# Main.net
KiCad netlist of a schematic drawn in Altium Designer
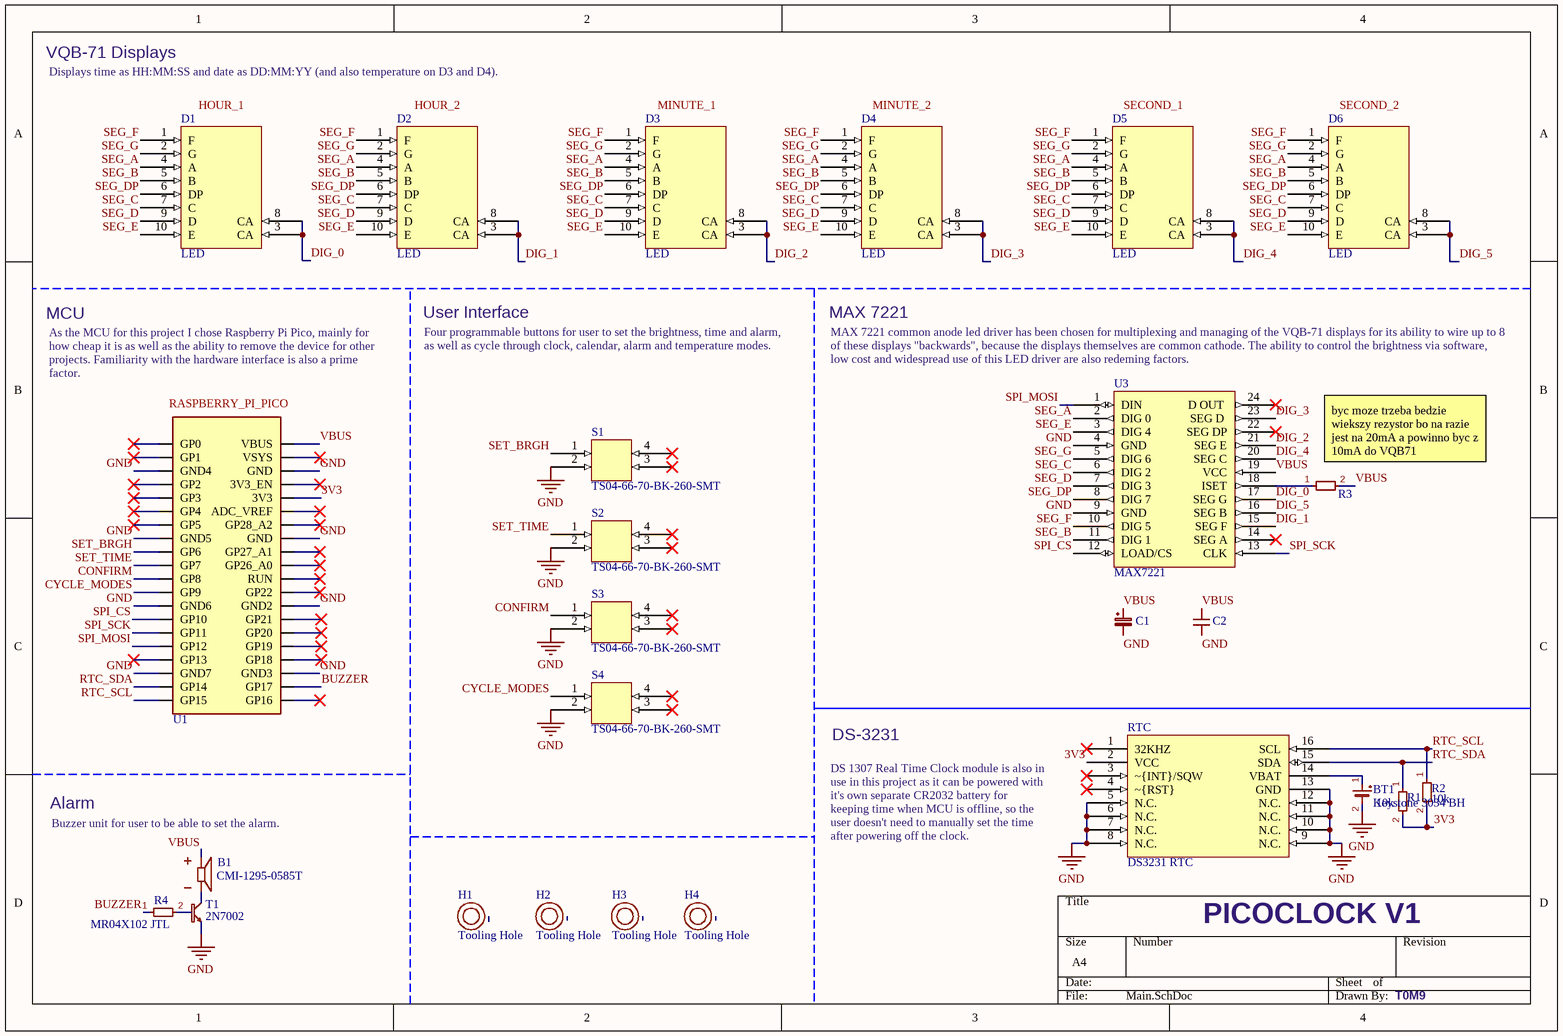
[diagram p0: Main.SchDoc]

(export (version "E")
  (design (tool "Eeschema 10.0.6"))
  (components
    (comp (ref "B1")
      (value "CMI-1295-0585T")
      (footprint "CMI-1295-0585T")
      (description "Buzzer")
      (libsource (lib "Schlib1") (part "CMI-1295-0585T"))
    )
    (comp (ref "BT1")
      (value "Keystone 3034 BH")
      (footprint "BAT_3034TR")
      (libsource (lib "Schlib1") (part "Keystone 3034 BH"))
    )
    (comp (ref "C1")
      (value "Electrolitic Capacitor 10uF")
      (footprint "CAPC2012X145N")
      (description "CGA4J1X7R0J106K125AC \r\n\r\n10u 6.3V 0805")
      (libsource (lib "Schlib1") (part "Electrolitic Capacitor 10uF"))
    )
    (comp (ref "C2")
      (value "UMK105B7104KVHF")
      (footprint "UMK105B7104KVHF")
      (description "0.1uF")
      (libsource (lib "Schlib1") (part "UMK105B7104KVHF"))
    )
    (comp (ref "D1")
      (value "LED")
      (footprint "LED_INND-TS56RAB")
      (description "VQB-71")
      (libsource (lib "Schlib1") (part "LED"))
    )
    (comp (ref "D2")
      (value "LED")
      (footprint "LED_INND-TS56RAB")
      (description "VQB-71")
      (libsource (lib "Schlib1") (part "LED"))
    )
    (comp (ref "D3")
      (value "LED")
      (footprint "LED_INND-TS56RAB")
      (description "VQB-71")
      (libsource (lib "Schlib1") (part "LED"))
    )
    (comp (ref "D4")
      (value "LED")
      (footprint "LED_INND-TS56RAB")
      (description "VQB-71")
      (libsource (lib "Schlib1") (part "LED"))
    )
    (comp (ref "D5")
      (value "LED")
      (footprint "LED_INND-TS56RAB")
      (description "VQB-71")
      (libsource (lib "Schlib1") (part "LED"))
    )
    (comp (ref "D6")
      (value "LED")
      (footprint "LED_INND-TS56RAB")
      (description "VQB-71")
      (libsource (lib "Schlib1") (part "LED"))
    )
    (comp (ref "H1")
      (value "Tooling Hole")
      (footprint "Tooling Hole")
      (libsource (lib "Schlib1") (part "Tooling Hole"))
    )
    (comp (ref "H2")
      (value "Tooling Hole")
      (footprint "Tooling Hole")
      (libsource (lib "Schlib1") (part "Tooling Hole"))
    )
    (comp (ref "H3")
      (value "Tooling Hole")
      (footprint "Tooling Hole")
      (libsource (lib "Schlib1") (part "Tooling Hole"))
    )
    (comp (ref "H4")
      (value "Tooling Hole")
      (footprint "Tooling Hole")
      (libsource (lib "Schlib1") (part "Tooling Hole"))
    )
    (comp (ref "R1")
      (value "10k")
      (footprint "MR04X102 JTL")
      (libsource (lib "Schlib1") (part "ESR01MZPF1002"))
    )
    (comp (ref "R2")
      (value "10k")
      (footprint "MR04X102 JTL")
      (libsource (lib "Schlib1") (part "ESR01MZPF1002"))
    )
    (comp (ref "R3")
      (value "CRCW040221K0FKEDC")
      (footprint "CRCW040221K0FKEDC")
      (description "21k")
      (libsource (lib "Schlib1") (part "CRCW040221K0FKEDC"))
    )
    (comp (ref "R4")
      (value "MR04X102 JTL")
      (footprint "MR04X102 JTL")
      (description "1k")
      (libsource (lib "Schlib1") (part "MR04X102 JTL"))
    )
    (comp (ref "RTC")
      (value "DS3231 RTC")
      (footprint "DS3231 RTC")
      (libsource (lib "Schlib1") (part "DS3231 RTC"))
    )
    (comp (ref "S1")
      (value "TS04-66-70-BK-260-SMT")
      (footprint "TS04-66-70-BK-260-SMT")
      (description "50mA 12VDC")
      (libsource (lib "Schlib1") (part "TS04-66-70-BK-260-SMT"))
    )
    (comp (ref "S2")
      (value "TS04-66-70-BK-260-SMT")
      (footprint "TS04-66-70-BK-260-SMT")
      (description "50mA 12VDC")
      (libsource (lib "Schlib1") (part "TS04-66-70-BK-260-SMT"))
    )
    (comp (ref "S3")
      (value "TS04-66-70-BK-260-SMT")
      (footprint "TS04-66-70-BK-260-SMT")
      (description "50mA 12VDC")
      (libsource (lib "Schlib1") (part "TS04-66-70-BK-260-SMT"))
    )
    (comp (ref "S4")
      (value "TS04-66-70-BK-260-SMT")
      (footprint "TS04-66-70-BK-260-SMT")
      (description "50mA 12VDC")
      (libsource (lib "Schlib1") (part "TS04-66-70-BK-260-SMT"))
    )
    (comp (ref "T1")
      (value "2N7002")
      (footprint "2N7002")
      (description "Transistor")
      (libsource (lib "Schlib1") (part "2N7002"))
    )
    (comp (ref "U1")
      (value "RASPBERRY_PI_PICO")
      (footprint "RASPBERRY_PI_PICO")
      (fields (field (name "MF") "Raspberry Pi") (field (name "MP") "RASPBERRY PI PICO"))
      (libsource (lib "Schlib1") (part "RASPBERRY_PI_PICO"))
    )
    (comp (ref "U3") (value "MAX7221") (footprint "MAX7221") (libsource (lib "Schlib1") (part "MAX7221")))
  )
  (nets
    (net (code "1") (name "/3V3") (class "Default")
      (node (ref "R1") (pin "2") (pinfunction "2_2") (pintype "passive"))
      (node (ref "R2") (pin "2") (pinfunction "2_2") (pintype "passive"))
      (node (ref "RTC") (pin "2") (pinfunction "VCC_2") (pintype "power_in"))
      (node (ref "U1") (pin "3V3") (pinfunction "3V3_3V3") (pintype "power_in"))
    )
    (net (code "2") (name "/BUZZER") (class "Default")
      (node (ref "R4") (pin "1") (pinfunction "1_1") (pintype "passive"))
      (node (ref "U1") (pin "GP17") (pinfunction "GP17_GP17") (pintype "bidirectional"))
    )
    (net (code "3") (name "/CONFIRM") (class "Default")
      (node (ref "S3") (pin "1") (pintype "input"))
      (node (ref "U1") (pin "GP8") (pinfunction "GP8_GP8") (pintype "bidirectional"))
    )
    (net (code "4") (name "/CYCLE_MODES") (class "Default")
      (node (ref "S4") (pin "1") (pintype "input"))
      (node (ref "U1") (pin "GP9") (pinfunction "GP9_GP9") (pintype "bidirectional"))
    )
    (net (code "5") (name "/DIG_0") (class "Default")
      (node (ref "D1") (pin "3") (pinfunction "CA_3") (pintype "input"))
      (node (ref "D1") (pin "8") (pinfunction "CA_8") (pintype "input"))
      (node (ref "U3") (pin "17") (pinfunction "SEG_G_17") (pintype "output"))
    )
    (net (code "6") (name "/DIG_1") (class "Default")
      (node (ref "D2") (pin "3") (pinfunction "CA_3") (pintype "input"))
      (node (ref "D2") (pin "8") (pinfunction "CA_8") (pintype "input"))
      (node (ref "U3") (pin "15") (pinfunction "SEG_F_15") (pintype "output"))
    )
    (net (code "7") (name "/DIG_2") (class "Default")
      (node (ref "D3") (pin "3") (pinfunction "CA_3") (pintype "input"))
      (node (ref "D3") (pin "8") (pinfunction "CA_8") (pintype "input"))
      (node (ref "U3") (pin "21") (pinfunction "SEG_E_21") (pintype "output"))
    )
    (net (code "8") (name "/DIG_3") (class "Default")
      (node (ref "D4") (pin "3") (pinfunction "CA_3") (pintype "input"))
      (node (ref "D4") (pin "8") (pinfunction "CA_8") (pintype "input"))
      (node (ref "U3") (pin "23") (pinfunction "SEG_D_23") (pintype "output"))
    )
    (net (code "9") (name "/DIG_4") (class "Default")
      (node (ref "D5") (pin "3") (pinfunction "CA_3") (pintype "input"))
      (node (ref "D5") (pin "8") (pinfunction "CA_8") (pintype "input"))
      (node (ref "U3") (pin "20") (pinfunction "SEG_C_20") (pintype "output"))
    )
    (net (code "10") (name "/DIG_5") (class "Default")
      (node (ref "D6") (pin "3") (pinfunction "CA_3") (pintype "input"))
      (node (ref "D6") (pin "8") (pinfunction "CA_8") (pintype "input"))
      (node (ref "U3") (pin "16") (pinfunction "SEG_B_16") (pintype "output"))
    )
    (net (code "11") (name "/RTC_SCL") (class "Default")
      (node (ref "R2") (pin "1") (pinfunction "1_1") (pintype "passive"))
      (node (ref "RTC") (pin "16") (pinfunction "SCL_16") (pintype "input"))
      (node (ref "U1") (pin "GP15") (pinfunction "GP15_GP15") (pintype "bidirectional"))
    )
    (net (code "12") (name "/RTC_SDA") (class "Default")
      (node (ref "R1") (pin "1") (pinfunction "1_1") (pintype "passive"))
      (node (ref "RTC") (pin "15") (pinfunction "SDA_15") (pintype "bidirectional"))
      (node (ref "U1") (pin "GP14") (pinfunction "GP14_GP14") (pintype "bidirectional"))
    )
    (net (code "13") (name "/SEG_A") (class "Default")
      (node (ref "D1") (pin "4") (pinfunction "A_4") (pintype "input"))
      (node (ref "D2") (pin "4") (pinfunction "A_4") (pintype "input"))
      (node (ref "D3") (pin "4") (pinfunction "A_4") (pintype "input"))
      (node (ref "D4") (pin "4") (pinfunction "A_4") (pintype "input"))
      (node (ref "D5") (pin "4") (pinfunction "A_4") (pintype "input"))
      (node (ref "D6") (pin "4") (pinfunction "A_4") (pintype "input"))
      (node (ref "U3") (pin "2") (pinfunction "DIG_0_2") (pintype "output"))
    )
    (net (code "14") (name "/SEG_B") (class "Default")
      (node (ref "D1") (pin "5") (pinfunction "B_5") (pintype "input"))
      (node (ref "D2") (pin "5") (pinfunction "B_5") (pintype "input"))
      (node (ref "D3") (pin "5") (pinfunction "B_5") (pintype "input"))
      (node (ref "D4") (pin "5") (pinfunction "B_5") (pintype "input"))
      (node (ref "D5") (pin "5") (pinfunction "B_5") (pintype "input"))
      (node (ref "D6") (pin "5") (pinfunction "B_5") (pintype "input"))
      (node (ref "U3") (pin "11") (pinfunction "DIG_1_11") (pintype "output"))
    )
    (net (code "15") (name "/SEG_C") (class "Default")
      (node (ref "D1") (pin "7") (pinfunction "C_7") (pintype "input"))
      (node (ref "D2") (pin "7") (pinfunction "C_7") (pintype "input"))
      (node (ref "D3") (pin "7") (pinfunction "C_7") (pintype "input"))
      (node (ref "D4") (pin "7") (pinfunction "C_7") (pintype "input"))
      (node (ref "D5") (pin "7") (pinfunction "C_7") (pintype "input"))
      (node (ref "D6") (pin "7") (pinfunction "C_7") (pintype "input"))
      (node (ref "U3") (pin "6") (pinfunction "DIG_2_6") (pintype "output"))
    )
    (net (code "16") (name "/SEG_D") (class "Default")
      (node (ref "D1") (pin "9") (pinfunction "D_9") (pintype "input"))
      (node (ref "D2") (pin "9") (pinfunction "D_9") (pintype "input"))
      (node (ref "D3") (pin "9") (pinfunction "D_9") (pintype "input"))
      (node (ref "D4") (pin "9") (pinfunction "D_9") (pintype "input"))
      (node (ref "D5") (pin "9") (pinfunction "D_9") (pintype "input"))
      (node (ref "D6") (pin "9") (pinfunction "D_9") (pintype "input"))
      (node (ref "U3") (pin "7") (pinfunction "DIG_3_7") (pintype "output"))
    )
    (net (code "17") (name "/SEG_DP") (class "Default")
      (node (ref "D1") (pin "6") (pinfunction "DP_6") (pintype "input"))
      (node (ref "D2") (pin "6") (pinfunction "DP_6") (pintype "input"))
      (node (ref "D3") (pin "6") (pinfunction "DP_6") (pintype "input"))
      (node (ref "D4") (pin "6") (pinfunction "DP_6") (pintype "input"))
      (node (ref "D5") (pin "6") (pinfunction "DP_6") (pintype "input"))
      (node (ref "D6") (pin "6") (pinfunction "DP_6") (pintype "input"))
      (node (ref "U3") (pin "8") (pinfunction "DIG_7_8") (pintype "output"))
    )
    (net (code "18") (name "/SEG_E") (class "Default")
      (node (ref "D1") (pin "10") (pinfunction "E_10") (pintype "input"))
      (node (ref "D2") (pin "10") (pinfunction "E_10") (pintype "input"))
      (node (ref "D3") (pin "10") (pinfunction "E_10") (pintype "input"))
      (node (ref "D4") (pin "10") (pinfunction "E_10") (pintype "input"))
      (node (ref "D5") (pin "10") (pinfunction "E_10") (pintype "input"))
      (node (ref "D6") (pin "10") (pinfunction "E_10") (pintype "input"))
      (node (ref "U3") (pin "3") (pinfunction "DIG_4_3") (pintype "output"))
    )
    (net (code "19") (name "/SEG_F") (class "Default")
      (node (ref "D1") (pin "1") (pinfunction "F_1") (pintype "input"))
      (node (ref "D2") (pin "1") (pinfunction "F_1") (pintype "input"))
      (node (ref "D3") (pin "1") (pinfunction "F_1") (pintype "input"))
      (node (ref "D4") (pin "1") (pinfunction "F_1") (pintype "input"))
      (node (ref "D5") (pin "1") (pinfunction "F_1") (pintype "input"))
      (node (ref "D6") (pin "1") (pinfunction "F_1") (pintype "input"))
      (node (ref "U3") (pin "10") (pinfunction "DIG_5_10") (pintype "output"))
    )
    (net (code "20") (name "/SEG_G") (class "Default")
      (node (ref "D1") (pin "2") (pinfunction "G_2") (pintype "input"))
      (node (ref "D2") (pin "2") (pinfunction "G_2") (pintype "input"))
      (node (ref "D3") (pin "2") (pinfunction "G_2") (pintype "input"))
      (node (ref "D4") (pin "2") (pinfunction "G_2") (pintype "input"))
      (node (ref "D5") (pin "2") (pinfunction "G_2") (pintype "input"))
      (node (ref "D6") (pin "2") (pinfunction "G_2") (pintype "input"))
      (node (ref "U3") (pin "5") (pinfunction "DIG_6_5") (pintype "output"))
    )
    (net (code "21") (name "/SET_BRGH") (class "Default")
      (node (ref "S1") (pin "1") (pintype "input"))
      (node (ref "U1") (pin "GP6") (pinfunction "GP6_GP6") (pintype "bidirectional"))
    )
    (net (code "22") (name "/SET_TIME") (class "Default")
      (node (ref "S2") (pin "1") (pintype "input"))
      (node (ref "U1") (pin "GP7") (pinfunction "GP7_GP7") (pintype "bidirectional"))
    )
    (net (code "23") (name "/SPI_CS") (class "Default")
      (node (ref "U1") (pin "GP10") (pinfunction "GP10_GP10") (pintype "bidirectional"))
      (node (ref "U3") (pin "12") (pinfunction "LOAD/CS_12") (pintype "bidirectional"))
    )
    (net (code "24") (name "/SPI_MOSI") (class "Default")
      (node (ref "U1") (pin "GP12") (pinfunction "GP12_GP12") (pintype "bidirectional"))
      (node (ref "U3") (pin "1") (pinfunction "DIN_1") (pintype "bidirectional"))
    )
    (net (code "25") (name "/SPI_SCK") (class "Default")
      (node (ref "U1") (pin "GP11") (pinfunction "GP11_GP11") (pintype "bidirectional"))
      (node (ref "U3") (pin "13") (pinfunction "CLK_13") (pintype "input"))
    )
    (net (code "26") (name "/VBUS") (class "Default")
      (node (ref "B1") (pin "P") (pinfunction "P_P") (pintype "passive"))
      (node (ref "C1") (pin "1") (pinfunction "1_1") (pintype "passive"))
      (node (ref "C2") (pin "1") (pinfunction "1_1") (pintype "passive"))
      (node (ref "R3") (pin "2") (pinfunction "2_2") (pintype "passive"))
      (node (ref "U1") (pin "VBUS") (pinfunction "VBUS_VBUS") (pintype "bidirectional"))
      (node (ref "U3") (pin "19") (pinfunction "VCC_19") (pintype "input"))
    )
    (net (code "27") (name "GND") (class "Default")
      (node (ref "BT1") (pin "2") (pinfunction "2_2") (pintype "passive"))
      (node (ref "C1") (pin "2") (pinfunction "2_2") (pintype "passive"))
      (node (ref "C2") (pin "2") (pinfunction "2_2") (pintype "passive"))
      (node (ref "RTC") (pin "10") (pinfunction "N.C._10") (pintype "input"))
      (node (ref "RTC") (pin "11") (pinfunction "N.C._11") (pintype "input"))
      (node (ref "RTC") (pin "12") (pinfunction "N.C._12") (pintype "input"))
      (node (ref "RTC") (pin "13") (pinfunction "GND_13") (pintype "power_in"))
      (node (ref "RTC") (pin "5") (pinfunction "N.C._5") (pintype "input"))
      (node (ref "RTC") (pin "6") (pinfunction "N.C._6") (pintype "input"))
      (node (ref "RTC") (pin "7") (pinfunction "N.C._7") (pintype "input"))
      (node (ref "RTC") (pin "8") (pinfunction "N.C._8") (pintype "input"))
      (node (ref "RTC") (pin "9") (pinfunction "N.C._9") (pintype "input"))
      (node (ref "S1") (pin "2") (pintype "input"))
      (node (ref "S2") (pin "2") (pintype "input"))
      (node (ref "S3") (pin "2") (pintype "input"))
      (node (ref "S4") (pin "2") (pintype "input"))
      (node (ref "T1") (pin "2") (pinfunction "S_2") (pintype "passive"))
      (node (ref "U1") (pin "GND") (pinfunction "GND_GND") (pintype "passive"))
      (node (ref "U1") (pin "GND2") (pinfunction "GND2_GND2") (pintype "passive"))
      (node (ref "U1") (pin "GND3") (pinfunction "GND3_GND3") (pintype "passive"))
      (node (ref "U1") (pin "GND4") (pinfunction "GND4_GND4") (pintype "passive"))
      (node (ref "U1") (pin "GND5") (pinfunction "GND5_GND5") (pintype "passive"))
      (node (ref "U1") (pin "GND6") (pinfunction "GND6_GND6") (pintype "passive"))
      (node (ref "U1") (pin "GND7") (pinfunction "GND7_GND7") (pintype "passive"))
      (node (ref "U3") (pin "4") (pinfunction "GND_4") (pintype "input"))
      (node (ref "U3") (pin "9") (pinfunction "GND_9") (pintype "input"))
    )
    (net (code "28") (name "Net-(RTC-VBAT)") (class "Default")
      (node (ref "BT1") (pin "1") (pinfunction "1_1") (pintype "passive"))
      (node (ref "RTC") (pin "14") (pinfunction "VBAT_14") (pintype "power_in"))
    )
    (net (code "29") (name "Net-(T1-D)") (class "Default")
      (node (ref "B1") (pin "N") (pinfunction "N_N") (pintype "passive"))
      (node (ref "T1") (pin "3") (pinfunction "D_3") (pintype "passive"))
    )
    (net (code "30") (name "Net-(T1-G)") (class "Default")
      (node (ref "R4") (pin "2") (pinfunction "2_2") (pintype "passive"))
      (node (ref "T1") (pin "1") (pinfunction "G_1") (pintype "passive"))
    )
    (net (code "31") (name "Net-(U3-ISET)") (class "Default")
      (node (ref "R3") (pin "1") (pinfunction "1_1") (pintype "passive"))
      (node (ref "U3") (pin "18") (pinfunction "ISET_18") (pintype "output"))
    )
    (net (code "32") (name "unconnected-(RTC-32KHZ-Pad1)") (class "Default")
      (node (ref "RTC") (pin "1") (pinfunction "32KHZ_1") (pintype "open_collector+no_connect"))
    )
    (net (code "33") (name "unconnected-(RTC-~{INT}{slash}SQW-Pad3)") (class "Default")
      (node (ref "RTC") (pin "3") (pinfunction "~{INT}/SQW_3") (pintype "input+no_connect"))
    )
    (net (code "34") (name "unconnected-(RTC-~{RST}-Pad4)") (class "Default")
      (node (ref "RTC") (pin "4") (pinfunction "~{RST}_4") (pintype "input+no_connect"))
    )
    (net (code "35") (name "unconnected-(S1-Pad3)") (class "Default")
      (node (ref "S1") (pin "3") (pintype "input+no_connect"))
    )
    (net (code "36") (name "unconnected-(S1-Pad4)") (class "Default")
      (node (ref "S1") (pin "4") (pintype "input+no_connect"))
    )
    (net (code "37") (name "unconnected-(S2-Pad3)") (class "Default")
      (node (ref "S2") (pin "3") (pintype "input+no_connect"))
    )
    (net (code "38") (name "unconnected-(S2-Pad4)") (class "Default")
      (node (ref "S2") (pin "4") (pintype "input+no_connect"))
    )
    (net (code "39") (name "unconnected-(S3-Pad3)") (class "Default")
      (node (ref "S3") (pin "3") (pintype "input+no_connect"))
    )
    (net (code "40") (name "unconnected-(S3-Pad4)") (class "Default")
      (node (ref "S3") (pin "4") (pintype "input+no_connect"))
    )
    (net (code "41") (name "unconnected-(S4-Pad3)") (class "Default")
      (node (ref "S4") (pin "3") (pintype "input+no_connect"))
    )
    (net (code "42") (name "unconnected-(S4-Pad4)") (class "Default")
      (node (ref "S4") (pin "4") (pintype "input+no_connect"))
    )
    (net (code "43") (name "unconnected-(U1-Pad3V3_EN)") (class "Default")
      (node (ref "U1") (pin "3V3_EN") (pinfunction "3V3_EN_3V3_EN") (pintype "bidirectional+no_connect"))
    )
    (net (code "44") (name "unconnected-(U1-PadADC_VREF)") (class "Default")
      (node (ref "U1") (pin "ADC_VREF") (pinfunction "ADC_VREF_ADC_VREF") (pintype "bidirectional+no_connect"))
    )
    (net (code "45") (name "unconnected-(U1-PadGP0)") (class "Default")
      (node (ref "U1") (pin "GP0") (pinfunction "GP0_GP0") (pintype "bidirectional+no_connect"))
    )
    (net (code "46") (name "unconnected-(U1-PadGP1)") (class "Default")
      (node (ref "U1") (pin "GP1") (pinfunction "GP1_GP1") (pintype "bidirectional+no_connect"))
    )
    (net (code "47") (name "unconnected-(U1-PadGP2)") (class "Default")
      (node (ref "U1") (pin "GP2") (pinfunction "GP2_GP2") (pintype "bidirectional+no_connect"))
    )
    (net (code "48") (name "unconnected-(U1-PadGP3)") (class "Default")
      (node (ref "U1") (pin "GP3") (pinfunction "GP3_GP3") (pintype "bidirectional+no_connect"))
    )
    (net (code "49") (name "unconnected-(U1-PadGP4)") (class "Default")
      (node (ref "U1") (pin "GP4") (pinfunction "GP4_GP4") (pintype "bidirectional+no_connect"))
    )
    (net (code "50") (name "unconnected-(U1-PadGP5)") (class "Default")
      (node (ref "U1") (pin "GP5") (pinfunction "GP5_GP5") (pintype "bidirectional+no_connect"))
    )
    (net (code "51") (name "unconnected-(U1-PadGP13)") (class "Default")
      (node (ref "U1") (pin "GP13") (pinfunction "GP13_GP13") (pintype "bidirectional+no_connect"))
    )
    (net (code "52") (name "unconnected-(U1-PadGP16)") (class "Default")
      (node (ref "U1") (pin "GP16") (pinfunction "GP16_GP16") (pintype "bidirectional+no_connect"))
    )
    (net (code "53") (name "unconnected-(U1-PadGP18)") (class "Default")
      (node (ref "U1") (pin "GP18") (pinfunction "GP18_GP18") (pintype "bidirectional+no_connect"))
    )
    (net (code "54") (name "unconnected-(U1-PadGP19)") (class "Default")
      (node (ref "U1") (pin "GP19") (pinfunction "GP19_GP19") (pintype "bidirectional+no_connect"))
    )
    (net (code "55") (name "unconnected-(U1-PadGP20)") (class "Default")
      (node (ref "U1") (pin "GP20") (pinfunction "GP20_GP20") (pintype "bidirectional+no_connect"))
    )
    (net (code "56") (name "unconnected-(U1-PadGP21)") (class "Default")
      (node (ref "U1") (pin "GP21") (pinfunction "GP21_GP21") (pintype "bidirectional+no_connect"))
    )
    (net (code "57") (name "unconnected-(U1-PadGP22)") (class "Default")
      (node (ref "U1") (pin "GP22") (pinfunction "GP22_GP22") (pintype "bidirectional+no_connect"))
    )
    (net (code "58") (name "unconnected-(U1-PadGP26_A0)") (class "Default")
      (node (ref "U1") (pin "GP26_A0") (pinfunction "GP26_A0_GP26_A0") (pintype "bidirectional+no_connect"))
    )
    (net (code "59") (name "unconnected-(U1-PadGP27_A1)") (class "Default")
      (node (ref "U1") (pin "GP27_A1") (pinfunction "GP27_A1_GP27_A1") (pintype "bidirectional+no_connect"))
    )
    (net (code "60") (name "unconnected-(U1-PadGP28_A2)") (class "Default")
      (node (ref "U1") (pin "GP28_A2") (pinfunction "GP28_A2_GP28_A2") (pintype "bidirectional+no_connect"))
    )
    (net (code "61") (name "unconnected-(U1-PadRUN)") (class "Default")
      (node (ref "U1") (pin "RUN") (pinfunction "RUN_RUN") (pintype "bidirectional+no_connect"))
    )
    (net (code "62") (name "unconnected-(U1-PadVSYS)") (class "Default")
      (node (ref "U1") (pin "VSYS") (pinfunction "VSYS_VSYS") (pintype "bidirectional+no_connect"))
    )
    (net (code "63") (name "unconnected-(U3-D_OUT-Pad24)") (class "Default")
      (node (ref "U3") (pin "24") (pinfunction "D_OUT_24") (pintype "output+no_connect"))
    )
    (net (code "64") (name "unconnected-(U3-SEG_A-Pad14)") (class "Default")
      (node (ref "U3") (pin "14") (pinfunction "SEG_A_14") (pintype "output+no_connect"))
    )
    (net (code "65") (name "unconnected-(U3-SEG_DP-Pad22)") (class "Default")
      (node (ref "U3") (pin "22") (pinfunction "SEG_DP_22") (pintype "output+no_connect"))
    )
  )
)
